# LoRa.net
KiCad netlist of a schematic drawn in Altium Designer
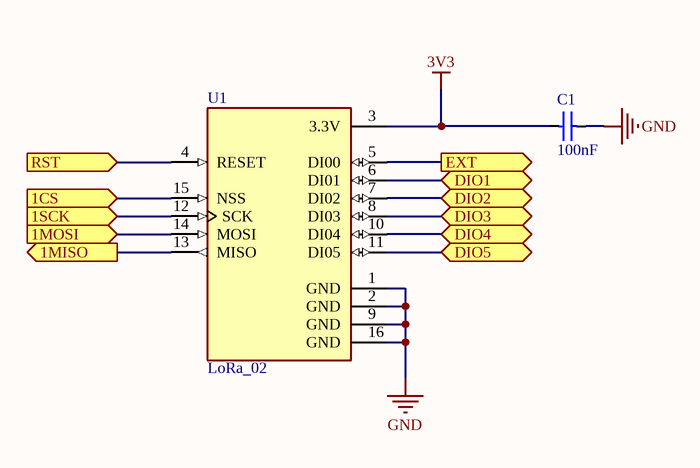
[diagram p0: LoRa.SchDoc]

(export (version "E")
  (design (tool "Eeschema 10.0.6"))
  (components
    (comp (ref "C1")
      (value "100nF")
      (footprint "CAP_0805")
      (description "Capacitor")
      (fields (field (name "PUBLISHER") "Altium Limited"))
      (libsource (lib "My Library") (part "CapSMD"))
    )
    (comp (ref "U1") (value "LoRa_02") (footprint "Ra-02") (libsource (lib "My Library") (part "LoRa_02")))
  )
  (nets
    (net (code "1") (name "/1CS") (class "Default")
      (node (ref "U1") (pin "15") (pinfunction "NSS_15") (pintype "input"))
    )
    (net (code "2") (name "/1MISO") (class "Default")
      (node (ref "U1") (pin "13") (pinfunction "MISO_13") (pintype "output"))
    )
    (net (code "3") (name "/1MOSI") (class "Default")
      (node (ref "U1") (pin "14") (pinfunction "MOSI_14") (pintype "input"))
    )
    (net (code "4") (name "/1SCK") (class "Default")
      (node (ref "U1") (pin "12") (pinfunction "SCK_12") (pintype "input"))
    )
    (net (code "5") (name "/DIO1") (class "Default")
      (node (ref "U1") (pin "6") (pinfunction "DI01_6") (pintype "bidirectional"))
    )
    (net (code "6") (name "/DIO2") (class "Default")
      (node (ref "U1") (pin "7") (pinfunction "DI02_7") (pintype "bidirectional"))
    )
    (net (code "7") (name "/DIO3") (class "Default")
      (node (ref "U1") (pin "8") (pinfunction "DI03_8") (pintype "bidirectional"))
    )
    (net (code "8") (name "/DIO4") (class "Default")
      (node (ref "U1") (pin "10") (pinfunction "DI04_10") (pintype "bidirectional"))
    )
    (net (code "9") (name "/DIO5") (class "Default")
      (node (ref "U1") (pin "11") (pinfunction "DI05_11") (pintype "bidirectional"))
    )
    (net (code "10") (name "/EXT") (class "Default")
      (node (ref "U1") (pin "5") (pinfunction "DI00_5") (pintype "bidirectional"))
    )
    (net (code "11") (name "/RST") (class "Default")
      (node (ref "U1") (pin "4") (pinfunction "RESET_4") (pintype "input"))
    )
    (net (code "12") (name "3V3") (class "Default")
      (node (ref "C1") (pin "1") (pinfunction "1_1") (pintype "passive"))
      (node (ref "U1") (pin "3") (pinfunction "3.3V_3") (pintype "power_in"))
    )
    (net (code "13") (name "GND") (class "Default")
      (node (ref "C1") (pin "2") (pinfunction "2_2") (pintype "passive"))
      (node (ref "U1") (pin "1") (pinfunction "GND_1") (pintype "power_in"))
      (node (ref "U1") (pin "16") (pinfunction "GND_16") (pintype "power_in"))
      (node (ref "U1") (pin "2") (pinfunction "GND_2") (pintype "power_in"))
      (node (ref "U1") (pin "9") (pinfunction "GND_9") (pintype "power_in"))
    )
  )
)
